# ETH_M_V1.net
KiCad netlist of a schematic drawn in Altium Designer
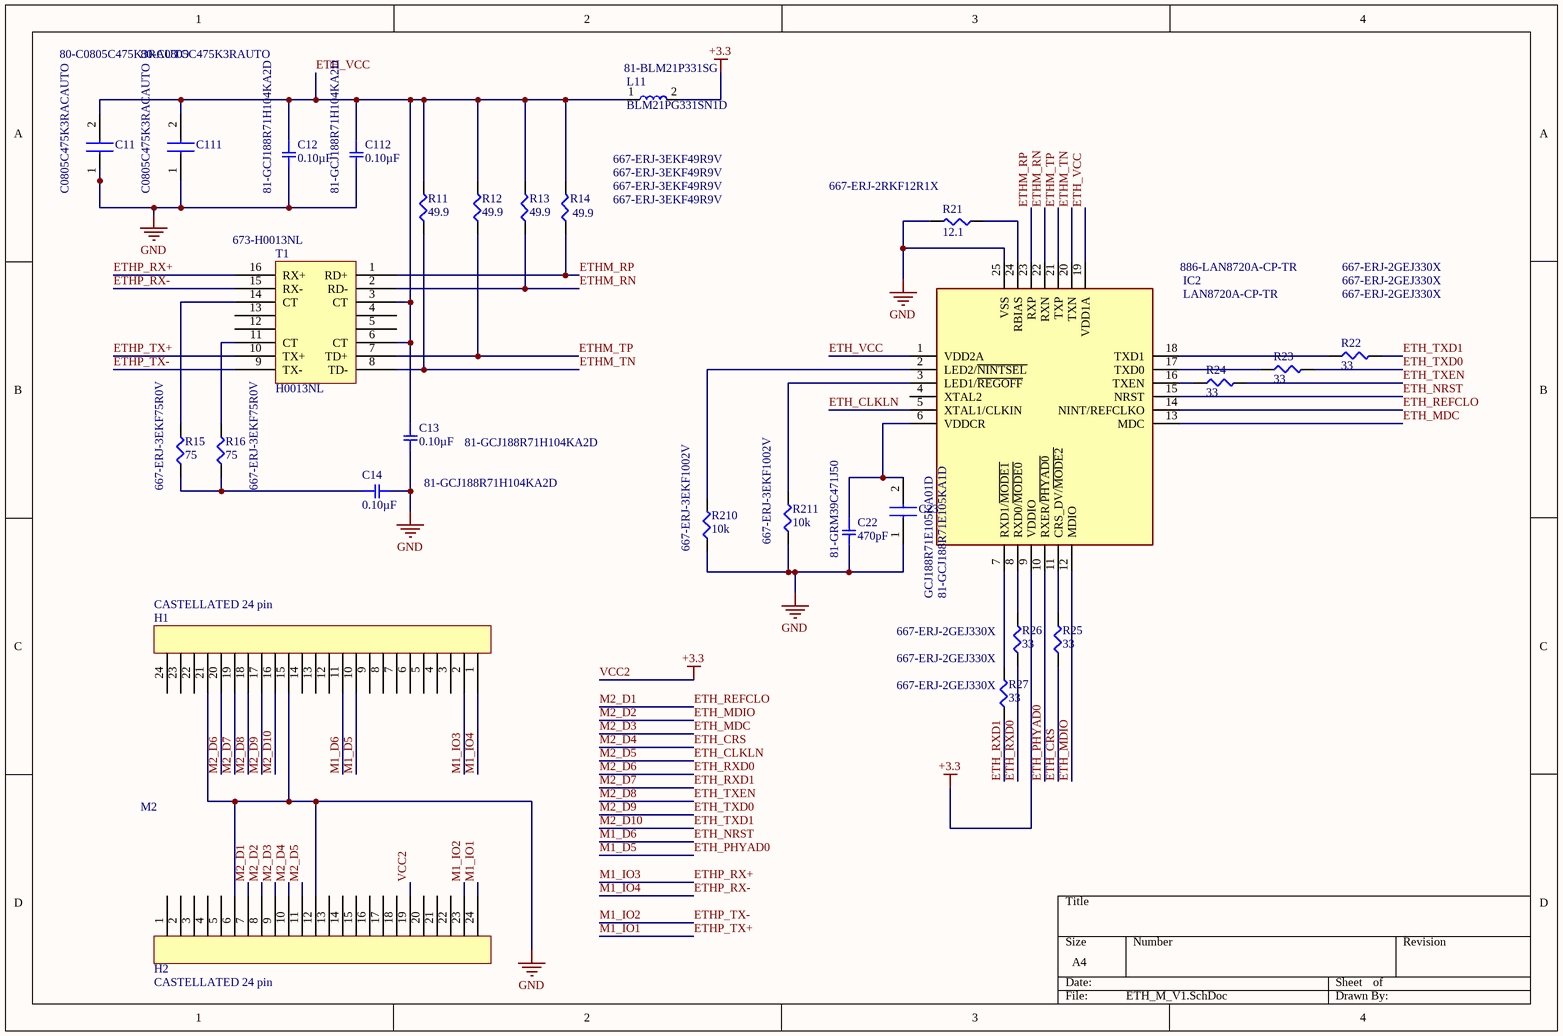
[diagram p0: ETH_M_V1.SchDoc]

(export (version "E")
  (design (tool "Eeschema 10.0.6"))
  (components
    (comp (ref "C11")
      (value "C0805C475K3RACAUTO")
      (footprint "SamacSys:CAPC2012X125N")
      (description "Capacitor")
      (fields
        (field (name "MOUSER2 PART NUMBER") "80-C0805C475K3RAUTO")
        (field (name "SUPPLIER PART NUMBER 1") "80-C0805C475K3RAUTO")
      )
      (libsource (lib "*") (part "C0805C475K3RACAUTO"))
    )
    (comp (ref "C12")
      (value "0.10µF")
      (footprint "SMD-0603C")
      (description "CAP CER 0.1UF 50V X7R 0603")
      (fields
        (field (name "DIGI-KEY PART NUMBER") "490-5798-1-ND")
        (field (name "PART NUMBER") "GCJ188R71H104KA12D")
        (field (name "SUPPLIER PART NUMBER 1") "81-GCJ188R71H104KA2D")
      )
      (libsource (lib "capacitor_murata_0603") (part "GCJ188R71H104KA12D"))
    )
    (comp (ref "C13")
      (value "0.10µF")
      (footprint "SMD-0603C")
      (description "CAP CER 0.1UF 50V X7R 0603")
      (fields
        (field (name "DIGI-KEY PART NUMBER") "490-5798-1-ND")
        (field (name "PART NUMBER") "GCJ188R71H104KA12D")
        (field (name "SUPPLIER PART NUMBER 1") "81-GCJ188R71H104KA2D")
      )
      (libsource (lib "capacitor_murata_0603") (part "GCJ188R71H104KA12D"))
    )
    (comp (ref "C14")
      (value "0.10µF")
      (footprint "SMD-0603C")
      (description "CAP CER 0.1UF 50V X7R 0603")
      (fields
        (field (name "DIGI-KEY PART NUMBER") "490-5798-1-ND")
        (field (name "PART NUMBER") "GCJ188R71H104KA12D")
        (field (name "SUPPLIER PART NUMBER 1") "81-GCJ188R71H104KA2D")
      )
      (libsource (lib "capacitor_murata_0603") (part "GCJ188R71H104KA12D"))
    )
    (comp (ref "C22")
      (value "470pF")
      (footprint "SMD-0603C")
      (description "CAP CER 470PF 50V NP0 0603")
      (fields
        (field (name "DIGI-KEY PART NUMBER") "490-1443-1-ND")
        (field (name "PART NUMBER") "GRM1885C1H471JA01D")
        (field (name "SUPPLIER PART NUMBER 1") "81-GRM39C471J50")
      )
      (libsource (lib "capacitor_murata_0603") (part "GRM1885C1H471JA01D"))
    )
    (comp (ref "C23")
      (value "GCJ188R71E105KA01D")
      (footprint "SamacSys:CAPC1608X100N")
      (description "Capacitor")
      (fields (field (name "SUPPLIER PART NUMBER 1") "81-GCJ188R71E105KA1D"))
      (libsource (lib "*") (part "GCJ188R71E105KA01D"))
    )
    (comp (ref "C111")
      (value "C0805C475K3RACAUTO")
      (footprint "SamacSys:CAPC2012X125N")
      (description "Capacitor")
      (fields
        (field (name "MOUSER2 PART NUMBER") "80-C0805C475K3RAUTO")
        (field (name "SUPPLIER PART NUMBER 1") "80-C0805C475K3RAUTO")
      )
      (libsource (lib "*") (part "C0805C475K3RACAUTO"))
    )
    (comp (ref "C112")
      (value "0.10µF")
      (footprint "SMD-0603C")
      (description "CAP CER 0.1UF 50V X7R 0603")
      (fields
        (field (name "DIGI-KEY PART NUMBER") "490-5798-1-ND")
        (field (name "PART NUMBER") "GCJ188R71H104KA12D")
        (field (name "SUPPLIER PART NUMBER 1") "81-GCJ188R71H104KA2D")
      )
      (libsource (lib "capacitor_murata_0603") (part "GCJ188R71H104KA12D"))
    )
    (comp (ref "H1")
      (value "CASTELLATED 24 pin")
      (footprint "CASTELLATED 24 pin")
      (libsource (lib "") (part "CASTELLATED 24 pin_1"))
    )
    (comp (ref "H2")
      (value "CASTELLATED 24 pin")
      (footprint "CASTELLATED 24 pin")
      (libsource (lib "USIB") (part "CASTELLATED 24 pin"))
    )
    (comp (ref "IC2")
      (value "LAN8720A-CP-TR")
      (footprint "SamacSys:QFN50P400X400X100-25N-D")
      (description "Integrated Circuit")
      (fields
        (field (name "MOUSER2 PART NUMBER") "886-LAN8720A-CP-TR")
        (field (name "SUPPLIER PART NUMBER 1") "886-LAN8720A-CP-TR")
      )
      (libsource (lib "*") (part "LAN8720A-CP-TR"))
    )
    (comp (ref "L11")
      (value "BLM21PG331SN1D")
      (footprint "INDC2012X87")
      (description "Ferrite Beads Multi-Layer 330Ohm 25% 100MHz 1.5A 70mOhm DCR 0805 Paper T/R")
      (fields
        (field (name "MF") "Murata")
        (field (name "DIGI-KEY_PART_NUMBER") "490-5988-1-ND")
        (field (name "SUPPLIER PART NUMBER 1") "81-BLM21P331SG")
      )
      (libsource (lib "BLM21PG331SN1D") (part "BLM21PG331SN1D"))
    )
    (comp (ref "R11")
      (value "49.9")
      (footprint "SMD-0603-RES")
      (description "RES SMD 49.9 OHM 1% 1/10W 0603")
      (fields
        (field (name "PART NUMBER") "ERJ-3EKF49R9V")
        (field (name "DIGI-KEY PART NUMBER") "P49.9HCT-ND")
        (field (name "SUPPLIER PART NUMBER 1") "667-ERJ-3EKF49R9V")
      )
      (libsource (lib "Panasonic_ERJ_0603") (part "ERJ-3EKF49R9V"))
    )
    (comp (ref "R12")
      (value "49.9")
      (footprint "SMD-0603-RES")
      (description "RES SMD 49.9 OHM 1% 1/10W 0603")
      (fields
        (field (name "PART NUMBER") "ERJ-3EKF49R9V")
        (field (name "DIGI-KEY PART NUMBER") "P49.9HCT-ND")
        (field (name "SUPPLIER PART NUMBER 1") "667-ERJ-3EKF49R9V")
      )
      (libsource (lib "Panasonic_ERJ_0603") (part "ERJ-3EKF49R9V"))
    )
    (comp (ref "R13")
      (value "49.9")
      (footprint "SMD-0603-RES")
      (description "RES SMD 49.9 OHM 1% 1/10W 0603")
      (fields
        (field (name "PART NUMBER") "ERJ-3EKF49R9V")
        (field (name "DIGI-KEY PART NUMBER") "P49.9HCT-ND")
        (field (name "SUPPLIER PART NUMBER 1") "667-ERJ-3EKF49R9V")
      )
      (libsource (lib "Panasonic_ERJ_0603") (part "ERJ-3EKF49R9V"))
    )
    (comp (ref "R14")
      (value "49.9")
      (footprint "SMD-0603-RES")
      (description "RES SMD 49.9 OHM 1% 1/10W 0603")
      (fields
        (field (name "PART NUMBER") "ERJ-3EKF49R9V")
        (field (name "DIGI-KEY PART NUMBER") "P49.9HCT-ND")
        (field (name "SUPPLIER PART NUMBER 1") "667-ERJ-3EKF49R9V")
      )
      (libsource (lib "Panasonic_ERJ_0603") (part "ERJ-3EKF49R9V"))
    )
    (comp (ref "R15")
      (value "75")
      (footprint "SMD-0603-RES")
      (description "RES SMD 75 OHM 1% 1/10W 0603")
      (fields
        (field (name "PART NUMBER") "ERJ-3EKF75R0V")
        (field (name "DIGI-KEY PART NUMBER") "P75.0HCT-ND")
        (field (name "SUPPLIER PART NUMBER 1") "667-ERJ-3EKF75R0V")
      )
      (libsource (lib "Panasonic_ERJ_0603") (part "ERJ-3EKF75R0V"))
    )
    (comp (ref "R16")
      (value "75")
      (footprint "SMD-0603-RES")
      (description "RES SMD 75 OHM 1% 1/10W 0603")
      (fields
        (field (name "PART NUMBER") "ERJ-3EKF75R0V")
        (field (name "DIGI-KEY PART NUMBER") "P75.0HCT-ND")
        (field (name "SUPPLIER PART NUMBER 1") "667-ERJ-3EKF75R0V")
      )
      (libsource (lib "Panasonic_ERJ_0603") (part "ERJ-3EKF75R0V"))
    )
    (comp (ref "R21")
      (value "12.1")
      (footprint "SMD-0402-RES")
      (description "RES SMD 12.1 OHM 1% 1/10W 0402")
      (fields
        (field (name "PART NUMBER") "ERJ-2RKF12R1X")
        (field (name "DIGI-KEY PART NUMBER") "P12.1LCT-ND")
        (field (name "SUPPLIER PART NUMBER 1") "667-ERJ-2RKF12R1X")
      )
      (libsource (lib "Panasonic_ERJ_0402") (part "ERJ-2RKF12R1X"))
    )
    (comp (ref "R22")
      (value "33")
      (footprint "SMD-0402-RES")
      (description "RES SMD 33 OHM 5% 1/10W 0402")
      (fields
        (field (name "PART NUMBER") "ERJ-2GEJ330X")
        (field (name "DIGI-KEY PART NUMBER") "P33JCT-ND")
        (field (name "SUPPLIER PART NUMBER 1") "667-ERJ-2GEJ330X")
      )
      (libsource (lib "Panasonic_ERJ_0402") (part "ERJ-2GEJ330X"))
    )
    (comp (ref "R23")
      (value "33")
      (footprint "SMD-0402-RES")
      (description "RES SMD 33 OHM 5% 1/10W 0402")
      (fields
        (field (name "PART NUMBER") "ERJ-2GEJ330X")
        (field (name "DIGI-KEY PART NUMBER") "P33JCT-ND")
        (field (name "SUPPLIER PART NUMBER 1") "667-ERJ-2GEJ330X")
      )
      (libsource (lib "Panasonic_ERJ_0402") (part "ERJ-2GEJ330X"))
    )
    (comp (ref "R24")
      (value "33")
      (footprint "SMD-0402-RES")
      (description "RES SMD 33 OHM 5% 1/10W 0402")
      (fields
        (field (name "PART NUMBER") "ERJ-2GEJ330X")
        (field (name "DIGI-KEY PART NUMBER") "P33JCT-ND")
        (field (name "SUPPLIER PART NUMBER 1") "667-ERJ-2GEJ330X")
      )
      (libsource (lib "Panasonic_ERJ_0402") (part "ERJ-2GEJ330X"))
    )
    (comp (ref "R25")
      (value "33")
      (footprint "SMD-0402-RES")
      (description "RES SMD 33 OHM 5% 1/10W 0402")
      (fields
        (field (name "PART NUMBER") "ERJ-2GEJ330X")
        (field (name "DIGI-KEY PART NUMBER") "P33JCT-ND")
        (field (name "SUPPLIER PART NUMBER 1") "667-ERJ-2GEJ330X")
      )
      (libsource (lib "Panasonic_ERJ_0402") (part "ERJ-2GEJ330X"))
    )
    (comp (ref "R26")
      (value "33")
      (footprint "SMD-0402-RES")
      (description "RES SMD 33 OHM 5% 1/10W 0402")
      (fields
        (field (name "PART NUMBER") "ERJ-2GEJ330X")
        (field (name "DIGI-KEY PART NUMBER") "P33JCT-ND")
        (field (name "SUPPLIER PART NUMBER 1") "667-ERJ-2GEJ330X")
      )
      (libsource (lib "Panasonic_ERJ_0402") (part "ERJ-2GEJ330X"))
    )
    (comp (ref "R27")
      (value "33")
      (footprint "SMD-0402-RES")
      (description "RES SMD 33 OHM 5% 1/10W 0402")
      (fields
        (field (name "PART NUMBER") "ERJ-2GEJ330X")
        (field (name "DIGI-KEY PART NUMBER") "P33JCT-ND")
        (field (name "SUPPLIER PART NUMBER 1") "667-ERJ-2GEJ330X")
      )
      (libsource (lib "Panasonic_ERJ_0402") (part "ERJ-2GEJ330X"))
    )
    (comp (ref "R210")
      (value "10k")
      (footprint "SMD-0603-RES")
      (description "RES SMD 10K OHM 1% 1/10W 0603")
      (fields
        (field (name "PART NUMBER") "ERJ-3EKF1002V")
        (field (name "DIGI-KEY PART NUMBER") "P10.0KHCT-ND")
        (field (name "SUPPLIER PART NUMBER 1") "667-ERJ-3EKF1002V")
      )
      (libsource (lib "Panasonic_ERJ_0603") (part "ERJ-3EKF1002V"))
    )
    (comp (ref "R211")
      (value "10k")
      (footprint "SMD-0603-RES")
      (description "RES SMD 10K OHM 1% 1/10W 0603")
      (fields
        (field (name "PART NUMBER") "ERJ-3EKF1002V")
        (field (name "DIGI-KEY PART NUMBER") "P10.0KHCT-ND")
        (field (name "SUPPLIER PART NUMBER 1") "667-ERJ-3EKF1002V")
      )
      (libsource (lib "Panasonic_ERJ_0603") (part "ERJ-3EKF1002V"))
    )
    (comp (ref "T1")
      (value "H0013NL")
      (footprint "SamacSys:H0013NL")
      (description "Transformer")
      (fields (field (name "SUPPLIER PART NUMBER 1") "673-H0013NL"))
      (libsource (lib "SamacSys") (part "H0013NL"))
    )
  )
  (nets
    (net (code "1") (name "+3.3") (class "Default")
      (node (ref "H2") (pin "19") (pintype "passive"))
      (node (ref "IC2") (pin "9") (pinfunction "VDDIO_9") (pintype "passive"))
      (node (ref "L11") (pin "2") (pinfunction "2_2") (pintype "passive"))
    )
    (net (code "2") (name "/ETHM_RN") (class "Default")
      (node (ref "IC2") (pin "22") (pinfunction "RXN_22") (pintype "passive"))
      (node (ref "R13") (pin "1") (pinfunction "1_1") (pintype "passive"))
      (node (ref "T1") (pin "2") (pinfunction "RD-_2") (pintype "passive"))
    )
    (net (code "3") (name "/ETHM_RP") (class "Default")
      (node (ref "IC2") (pin "23") (pinfunction "RXP_23") (pintype "passive"))
      (node (ref "R14") (pin "1") (pinfunction "1_1") (pintype "passive"))
      (node (ref "T1") (pin "1") (pinfunction "RD+_1") (pintype "passive"))
    )
    (net (code "4") (name "/ETHM_TN") (class "Default")
      (node (ref "IC2") (pin "20") (pinfunction "TXN_20") (pintype "passive"))
      (node (ref "R11") (pin "1") (pinfunction "1_1") (pintype "passive"))
      (node (ref "T1") (pin "8") (pinfunction "TD-_8") (pintype "passive"))
    )
    (net (code "5") (name "/ETHM_TP") (class "Default")
      (node (ref "IC2") (pin "21") (pinfunction "TXP_21") (pintype "passive"))
      (node (ref "R12") (pin "1") (pinfunction "1_1") (pintype "passive"))
      (node (ref "T1") (pin "7") (pinfunction "TD+_7") (pintype "passive"))
    )
    (net (code "6") (name "/ETHP_RX+") (class "Default")
      (node (ref "H1") (pin "2") (pintype "passive"))
      (node (ref "T1") (pin "16") (pinfunction "RX+_16") (pintype "passive"))
    )
    (net (code "7") (name "/ETHP_RX-") (class "Default")
      (node (ref "H1") (pin "1") (pintype "passive"))
      (node (ref "T1") (pin "15") (pinfunction "RX-_15") (pintype "passive"))
    )
    (net (code "8") (name "/ETHP_TX+") (class "Default")
      (node (ref "H2") (pin "24") (pintype "passive"))
      (node (ref "T1") (pin "10") (pinfunction "TX+_10") (pintype "passive"))
    )
    (net (code "9") (name "/ETHP_TX-") (class "Default")
      (node (ref "H2") (pin "23") (pintype "passive"))
      (node (ref "T1") (pin "9") (pinfunction "TX-_9") (pintype "passive"))
    )
    (net (code "10") (name "/ETH_CLKLN") (class "Default")
      (node (ref "H2") (pin "11") (pintype "passive"))
      (node (ref "IC2") (pin "5") (pinfunction "XTAL1/CLKIN_5") (pintype "passive"))
    )
    (net (code "11") (name "/ETH_CRS") (class "Default")
      (node (ref "H2") (pin "10") (pintype "passive"))
      (node (ref "R25") (pin "1") (pinfunction "1_1") (pintype "passive"))
    )
    (net (code "12") (name "/ETH_MDC") (class "Default")
      (node (ref "H2") (pin "9") (pintype "passive"))
      (node (ref "IC2") (pin "13") (pinfunction "MDC_13") (pintype "passive"))
    )
    (net (code "13") (name "/ETH_MDIO") (class "Default")
      (node (ref "H2") (pin "8") (pintype "passive"))
      (node (ref "IC2") (pin "12") (pinfunction "MDIO_12") (pintype "passive"))
    )
    (net (code "14") (name "/ETH_NRST") (class "Default")
      (node (ref "H1") (pin "11") (pintype "passive"))
      (node (ref "IC2") (pin "15") (pinfunction "NRST_15") (pintype "passive"))
    )
    (net (code "15") (name "/ETH_PHYAD0") (class "Default")
      (node (ref "H1") (pin "10") (pintype "passive"))
      (node (ref "IC2") (pin "10") (pinfunction "RXER/~{PHYAD0}_10") (pintype "passive"))
    )
    (net (code "16") (name "/ETH_REFCLO") (class "Default")
      (node (ref "H2") (pin "7") (pintype "passive"))
      (node (ref "IC2") (pin "14") (pinfunction "NINT/REFCLKO_14") (pintype "passive"))
    )
    (net (code "17") (name "/ETH_RXD0") (class "Default")
      (node (ref "H1") (pin "20") (pintype "passive"))
      (node (ref "R26") (pin "1") (pinfunction "1_1") (pintype "passive"))
    )
    (net (code "18") (name "/ETH_RXD1") (class "Default")
      (node (ref "H1") (pin "19") (pintype "passive"))
      (node (ref "R27") (pin "1") (pinfunction "1_1") (pintype "passive"))
    )
    (net (code "19") (name "/ETH_TXD0") (class "Default")
      (node (ref "H1") (pin "17") (pintype "passive"))
      (node (ref "R23") (pin "2") (pinfunction "2_2") (pintype "passive"))
    )
    (net (code "20") (name "/ETH_TXD1") (class "Default")
      (node (ref "H1") (pin "16") (pintype "passive"))
      (node (ref "R22") (pin "2") (pinfunction "2_2") (pintype "passive"))
    )
    (net (code "21") (name "/ETH_TXEN") (class "Default")
      (node (ref "H1") (pin "18") (pintype "passive"))
      (node (ref "R24") (pin "2") (pinfunction "2_2") (pintype "passive"))
    )
    (net (code "22") (name "/ETH_VCC") (class "Default")
      (node (ref "C11") (pin "2") (pinfunction "2_2") (pintype "passive"))
      (node (ref "C111") (pin "2") (pinfunction "2_2") (pintype "passive"))
      (node (ref "C112") (pin "1") (pinfunction "1_1") (pintype "passive"))
      (node (ref "C12") (pin "1") (pinfunction "1_1") (pintype "passive"))
      (node (ref "C13") (pin "1") (pinfunction "1_1") (pintype "passive"))
      (node (ref "IC2") (pin "1") (pinfunction "VDD2A_1") (pintype "passive"))
      (node (ref "IC2") (pin "19") (pinfunction "VDD1A_19") (pintype "passive"))
      (node (ref "L11") (pin "1") (pinfunction "1_1") (pintype "passive"))
      (node (ref "R11") (pin "2") (pinfunction "2_2") (pintype "passive"))
      (node (ref "R12") (pin "2") (pinfunction "2_2") (pintype "passive"))
      (node (ref "R13") (pin "2") (pinfunction "2_2") (pintype "passive"))
      (node (ref "R14") (pin "2") (pinfunction "2_2") (pintype "passive"))
      (node (ref "T1") (pin "3") (pinfunction "CT_3") (pintype "passive"))
      (node (ref "T1") (pin "6") (pinfunction "CT_6") (pintype "passive"))
    )
    (net (code "23") (name "GND") (class "Default")
      (node (ref "C11") (pin "1") (pinfunction "1_1") (pintype "passive"))
      (node (ref "C111") (pin "1") (pinfunction "1_1") (pintype "passive"))
      (node (ref "C112") (pin "2") (pinfunction "2_2") (pintype "passive"))
      (node (ref "C12") (pin "2") (pinfunction "2_2") (pintype "passive"))
      (node (ref "C13") (pin "2") (pinfunction "2_2") (pintype "passive"))
      (node (ref "C14") (pin "2") (pinfunction "2_2") (pintype "passive"))
      (node (ref "C22") (pin "2") (pinfunction "2_2") (pintype "passive"))
      (node (ref "C23") (pin "1") (pinfunction "1_1") (pintype "passive"))
      (node (ref "H1") (pin "15") (pintype "passive"))
      (node (ref "H1") (pin "21") (pintype "passive"))
      (node (ref "H2") (pin "12") (pintype "passive"))
      (node (ref "H2") (pin "6") (pintype "passive"))
      (node (ref "IC2") (pin "25") (pinfunction "VSS_25") (pintype "passive"))
      (node (ref "R21") (pin "2") (pinfunction "2_2") (pintype "passive"))
      (node (ref "R210") (pin "1") (pinfunction "1_1") (pintype "passive"))
      (node (ref "R211") (pin "1") (pinfunction "1_1") (pintype "passive"))
    )
    (net (code "24") (name "Net-(C14-Pad1)") (class "Default")
      (node (ref "C14") (pin "1") (pinfunction "1_1") (pintype "passive"))
      (node (ref "R15") (pin "1") (pinfunction "1_1") (pintype "passive"))
      (node (ref "R16") (pin "1") (pinfunction "1_1") (pintype "passive"))
    )
    (net (code "25") (name "Net-(IC2-CRS_DV{slash}~{MODE2})") (class "Default")
      (node (ref "IC2") (pin "11") (pinfunction "CRS_DV/~{MODE2}_11") (pintype "passive"))
      (node (ref "R25") (pin "2") (pinfunction "2_2") (pintype "passive"))
    )
    (net (code "26") (name "Net-(IC2-LED1{slash}~{REGOFF})") (class "Default")
      (node (ref "IC2") (pin "3") (pinfunction "LED1/~{REGOFF}_3") (pintype "passive"))
      (node (ref "R211") (pin "2") (pinfunction "2_2") (pintype "passive"))
    )
    (net (code "27") (name "Net-(IC2-LED2{slash}~{NINTSEL})") (class "Default")
      (node (ref "IC2") (pin "2") (pinfunction "LED2/~{NINTSEL}_2") (pintype "passive"))
      (node (ref "R210") (pin "2") (pinfunction "2_2") (pintype "passive"))
    )
    (net (code "28") (name "Net-(IC2-RBIAS)") (class "Default")
      (node (ref "IC2") (pin "24") (pinfunction "RBIAS_24") (pintype "passive"))
      (node (ref "R21") (pin "1") (pinfunction "1_1") (pintype "passive"))
    )
    (net (code "29") (name "Net-(IC2-RXD0{slash}~{MODE0})") (class "Default")
      (node (ref "IC2") (pin "8") (pinfunction "RXD0/~{MODE0}_8") (pintype "passive"))
      (node (ref "R26") (pin "2") (pinfunction "2_2") (pintype "passive"))
    )
    (net (code "30") (name "Net-(IC2-RXD1{slash}~{MODE1})") (class "Default")
      (node (ref "IC2") (pin "7") (pinfunction "RXD1/~{MODE1}_7") (pintype "passive"))
      (node (ref "R27") (pin "2") (pinfunction "2_2") (pintype "passive"))
    )
    (net (code "31") (name "Net-(IC2-TXD0)") (class "Default")
      (node (ref "IC2") (pin "17") (pinfunction "TXD0_17") (pintype "passive"))
      (node (ref "R23") (pin "1") (pinfunction "1_1") (pintype "passive"))
    )
    (net (code "32") (name "Net-(IC2-TXD1)") (class "Default")
      (node (ref "IC2") (pin "18") (pinfunction "TXD1_18") (pintype "passive"))
      (node (ref "R22") (pin "1") (pinfunction "1_1") (pintype "passive"))
    )
    (net (code "33") (name "Net-(IC2-TXEN)") (class "Default")
      (node (ref "IC2") (pin "16") (pinfunction "TXEN_16") (pintype "passive"))
      (node (ref "R24") (pin "1") (pinfunction "1_1") (pintype "passive"))
    )
    (net (code "34") (name "Net-(IC2-VDDCR)") (class "Default")
      (node (ref "C22") (pin "1") (pinfunction "1_1") (pintype "passive"))
      (node (ref "C23") (pin "2") (pinfunction "2_2") (pintype "passive"))
      (node (ref "IC2") (pin "6") (pinfunction "VDDCR_6") (pintype "passive"))
    )
    (net (code "35") (name "Net-(R15-Pad2)") (class "Default")
      (node (ref "R15") (pin "2") (pinfunction "2_2") (pintype "passive"))
      (node (ref "T1") (pin "14") (pinfunction "CT_14") (pintype "passive"))
    )
    (net (code "36") (name "Net-(R16-Pad2)") (class "Default")
      (node (ref "R16") (pin "2") (pinfunction "2_2") (pintype "passive"))
      (node (ref "T1") (pin "11") (pinfunction "CT_11") (pintype "passive"))
    )
    (net (code "37") (name "unconnected-(H1-Pad3)") (class "Default")
      (node (ref "H1") (pin "3") (pintype "passive"))
    )
    (net (code "38") (name "unconnected-(H1-Pad4)") (class "Default")
      (node (ref "H1") (pin "4") (pintype "passive"))
    )
    (net (code "39") (name "unconnected-(H1-Pad5)") (class "Default")
      (node (ref "H1") (pin "5") (pintype "passive"))
    )
    (net (code "40") (name "unconnected-(H1-Pad6)") (class "Default")
      (node (ref "H1") (pin "6") (pintype "passive"))
    )
    (net (code "41") (name "unconnected-(H1-Pad7)") (class "Default")
      (node (ref "H1") (pin "7") (pintype "passive"))
    )
    (net (code "42") (name "unconnected-(H1-Pad8)") (class "Default")
      (node (ref "H1") (pin "8") (pintype "passive"))
    )
    (net (code "43") (name "unconnected-(H1-Pad9)") (class "Default")
      (node (ref "H1") (pin "9") (pintype "passive"))
    )
    (net (code "44") (name "unconnected-(H1-Pad12)") (class "Default")
      (node (ref "H1") (pin "12") (pintype "passive"))
    )
    (net (code "45") (name "unconnected-(H1-Pad13)") (class "Default")
      (node (ref "H1") (pin "13") (pintype "passive"))
    )
    (net (code "46") (name "unconnected-(H1-Pad14)") (class "Default")
      (node (ref "H1") (pin "14") (pintype "passive"))
    )
    (net (code "47") (name "unconnected-(H1-Pad22)") (class "Default")
      (node (ref "H1") (pin "22") (pintype "passive"))
    )
    (net (code "48") (name "unconnected-(H1-Pad23)") (class "Default")
      (node (ref "H1") (pin "23") (pintype "passive"))
    )
    (net (code "49") (name "unconnected-(H1-Pad24)") (class "Default")
      (node (ref "H1") (pin "24") (pintype "passive"))
    )
    (net (code "50") (name "unconnected-(H2-Pad1)") (class "Default")
      (node (ref "H2") (pin "1") (pintype "passive"))
    )
    (net (code "51") (name "unconnected-(H2-Pad2)") (class "Default")
      (node (ref "H2") (pin "2") (pintype "passive"))
    )
    (net (code "52") (name "unconnected-(H2-Pad3)") (class "Default")
      (node (ref "H2") (pin "3") (pintype "passive"))
    )
    (net (code "53") (name "unconnected-(H2-Pad4)") (class "Default")
      (node (ref "H2") (pin "4") (pintype "passive"))
    )
    (net (code "54") (name "unconnected-(H2-Pad5)") (class "Default")
      (node (ref "H2") (pin "5") (pintype "passive"))
    )
    (net (code "55") (name "unconnected-(H2-Pad13)") (class "Default")
      (node (ref "H2") (pin "13") (pintype "passive"))
    )
    (net (code "56") (name "unconnected-(H2-Pad14)") (class "Default")
      (node (ref "H2") (pin "14") (pintype "passive"))
    )
    (net (code "57") (name "unconnected-(H2-Pad15)") (class "Default")
      (node (ref "H2") (pin "15") (pintype "passive"))
    )
    (net (code "58") (name "unconnected-(H2-Pad16)") (class "Default")
      (node (ref "H2") (pin "16") (pintype "passive"))
    )
    (net (code "59") (name "unconnected-(H2-Pad17)") (class "Default")
      (node (ref "H2") (pin "17") (pintype "passive"))
    )
    (net (code "60") (name "unconnected-(H2-Pad18)") (class "Default")
      (node (ref "H2") (pin "18") (pintype "passive"))
    )
    (net (code "61") (name "unconnected-(H2-Pad20)") (class "Default")
      (node (ref "H2") (pin "20") (pintype "passive"))
    )
    (net (code "62") (name "unconnected-(H2-Pad21)") (class "Default")
      (node (ref "H2") (pin "21") (pintype "passive"))
    )
    (net (code "63") (name "unconnected-(H2-Pad22)") (class "Default")
      (node (ref "H2") (pin "22") (pintype "passive"))
    )
    (net (code "64") (name "unconnected-(IC2-XTAL2-Pad4)") (class "Default")
      (node (ref "IC2") (pin "4") (pinfunction "XTAL2_4") (pintype "passive"))
    )
    (net (code "65") (name "unconnected-(T1-Pad4)") (class "Default")
      (node (ref "T1") (pin "4") (pintype "passive"))
    )
    (net (code "66") (name "unconnected-(T1-Pad5)") (class "Default")
      (node (ref "T1") (pin "5") (pintype "passive"))
    )
    (net (code "67") (name "unconnected-(T1-Pad12)") (class "Default")
      (node (ref "T1") (pin "12") (pintype "passive"))
    )
    (net (code "68") (name "unconnected-(T1-Pad13)") (class "Default")
      (node (ref "T1") (pin "13") (pintype "passive"))
    )
  )
)
